# untitled.net
KiCad netlist of a schematic drawn in EAGLE
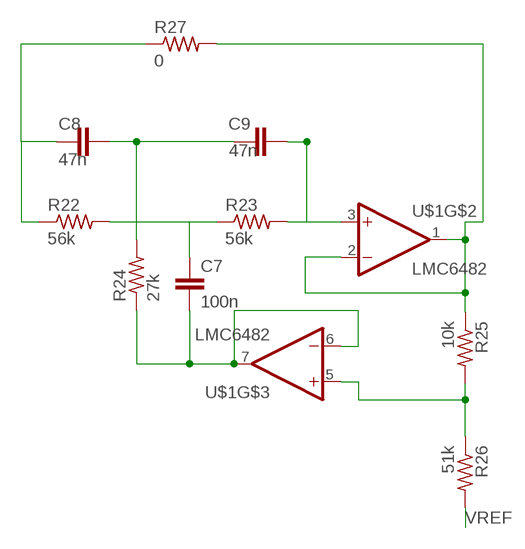
[diagram p0: schematic, sheet 1]

(export (version "E")
  (design (tool "Eeschema 10.0.6"))
  (components
    (comp (ref "C7")
      (value "100n")
      (footprint "eagle-import:C5B3")
      (libsource (lib "eagle-import") (part "C5/3"))
    )
    (comp (ref "C8")
      (value "47n")
      (footprint "eagle-import:C5B3")
      (libsource (lib "eagle-import") (part "C5/3"))
    )
    (comp (ref "C9")
      (value "47n")
      (footprint "eagle-import:C5B3")
      (libsource (lib "eagle-import") (part "C5/3"))
    )
    (comp (ref "R22")
      (value "56k")
      (footprint "eagle-import:0207_7")
      (libsource (lib "eagle-import") (part "R-US_0207/7"))
    )
    (comp (ref "R23")
      (value "56k")
      (footprint "eagle-import:0207_7")
      (libsource (lib "eagle-import") (part "R-US_0207/7"))
    )
    (comp (ref "R24")
      (value "27k")
      (footprint "eagle-import:0207_7")
      (libsource (lib "eagle-import") (part "R-US_0207/7"))
    )
    (comp (ref "R25")
      (value "10k")
      (footprint "eagle-import:0207_7")
      (libsource (lib "eagle-import") (part "R-US_0207/7"))
    )
    (comp (ref "R26")
      (value "51k")
      (footprint "eagle-import:0207_7")
      (libsource (lib "eagle-import") (part "R-US_0207/7"))
    )
    (comp (ref "R27")
      (value "0")
      (footprint "eagle-import:0207_7")
      (libsource (lib "eagle-import") (part "R-US_0207/7"))
    )
    (comp (ref "U$1")
      (value "LMC6482")
      (footprint "eagle-import:SO8")
      (libsource (lib "eagle-import") (part "LMC6482"))
    )
  )
  (nets
    (net (code "1") (name "/VREF") (class "Default")
      (node (ref "R26") (pin "2") (pinfunction "2_2") (pintype "passive"))
    )
    (net (code "2") (name "Net-(C7-Pad1)") (class "Default")
      (node (ref "C7") (pin "1") (pinfunction "1_1") (pintype "passive"))
      (node (ref "R22") (pin "2") (pinfunction "2_2") (pintype "passive"))
      (node (ref "R23") (pin "1") (pinfunction "1_1") (pintype "passive"))
    )
    (net (code "3") (name "Net-(C8-Pad1)") (class "Default")
      (node (ref "C8") (pin "1") (pinfunction "1_1") (pintype "passive"))
      (node (ref "C9") (pin "1") (pinfunction "1_1") (pintype "passive"))
      (node (ref "R24") (pin "2") (pinfunction "2_2") (pintype "passive"))
    )
    (net (code "4") (name "Net-(C8-Pad2)") (class "Default")
      (node (ref "C8") (pin "2") (pinfunction "2_2") (pintype "passive"))
      (node (ref "R22") (pin "1") (pinfunction "1_1") (pintype "passive"))
      (node (ref "R27") (pin "1") (pinfunction "1_1") (pintype "passive"))
    )
    (net (code "5") (name "Net-(U$1B-+IN)") (class "Default")
      (node (ref "C9") (pin "2") (pinfunction "2_2") (pintype "passive"))
      (node (ref "R23") (pin "2") (pinfunction "2_2") (pintype "passive"))
      (node (ref "U$1") (pin "3") (pinfunction "+IN_3") (pintype "input"))
    )
    (net (code "6") (name "Net-(U$1B--IN)") (class "Default")
      (node (ref "R25") (pin "1") (pinfunction "1_1") (pintype "passive"))
      (node (ref "R27") (pin "2") (pinfunction "2_2") (pintype "passive"))
      (node (ref "U$1") (pin "1") (pinfunction "OUT_1") (pintype "output"))
      (node (ref "U$1") (pin "2") (pinfunction "-IN_2") (pintype "input"))
    )
    (net (code "7") (name "Net-(U$1C-+IN)") (class "Default")
      (node (ref "R25") (pin "2") (pinfunction "2_2") (pintype "passive"))
      (node (ref "R26") (pin "1") (pinfunction "1_1") (pintype "passive"))
      (node (ref "U$1") (pin "5") (pinfunction "+IN_5") (pintype "input"))
    )
    (net (code "8") (name "Net-(U$1C--IN)") (class "Default")
      (node (ref "C7") (pin "2") (pinfunction "2_2") (pintype "passive"))
      (node (ref "R24") (pin "1") (pinfunction "1_1") (pintype "passive"))
      (node (ref "U$1") (pin "6") (pinfunction "-IN_6") (pintype "input"))
      (node (ref "U$1") (pin "7") (pinfunction "OUT_7") (pintype "output"))
    )
  )
)
